# LM35.net
KiCad netlist of a schematic drawn in Altium Designer
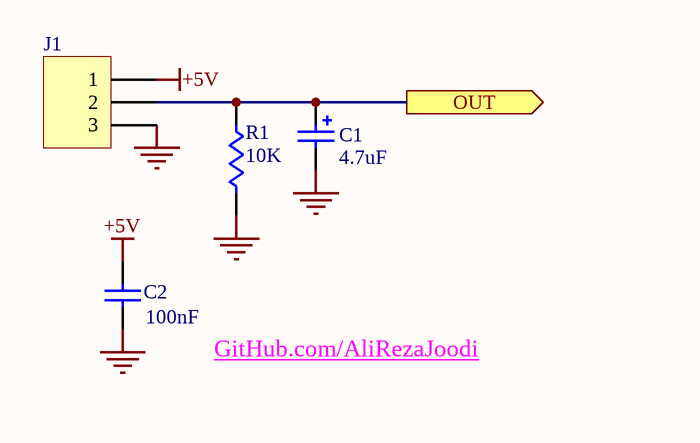
[diagram p0: LM35.SchDoc]

(export (version "E")
  (design (tool "Eeschema 10.0.6"))
  (components
    (comp (ref "C1")
      (value "4.7uF")
      (footprint "CAPPR2.5-6.3x5")
      (description "Polarized Capacitor (Radial)")
      (fields
        (field (name "MANUFACTURER") "Generic Components")
        (field (name "Comment") "Capacitor")
        (field (name "PUBLISHER") "Altium Limited")
      )
      (libsource (lib "Miscellaneous Devices") (part "Cap Pol1"))
    )
    (comp (ref "C2")
      (value "100nF")
      (footprint "CAPNTO2.54-3.05x1.78A")
      (description "Capacitor")
      (fields (field (name "PUBLISHER") "Altium Limited"))
      (libsource (lib "Miscellaneous Devices") (part "Cap"))
    )
    (comp (ref "J1")
      (value "Header")
      (footprint "Fonics_3PIN_1")
      (description "Header, 3-Pin")
      (fields (field (name "MANUFACTURER") "Generic Components") (field (name "PUBLISHER") "Altium Limited"))
      (libsource (lib "Miscellaneous Connectors") (part "Header 3"))
    )
    (comp (ref "R1")
      (value "10K")
      (footprint "AXIAL-0.4")
      (description "Resistor")
      (fields (field (name "MANUFACTURER") "Generic Components") (field (name "PUBLISHER") "Altium Limited"))
      (libsource (lib "Miscellaneous Devices") (part "Res1"))
    )
  )
  (nets
    (net (code "1") (name "+5V") (class "Default")
      (node (ref "C2") (pin "1") (pinfunction "1_1") (pintype "passive"))
      (node (ref "J1") (pin "1") (pinfunction "1_1") (pintype "passive"))
    )
    (net (code "2") (name "/OUT") (class "Default")
      (node (ref "C1") (pin "1") (pinfunction "1_1") (pintype "passive"))
      (node (ref "J1") (pin "2") (pinfunction "2_2") (pintype "passive"))
      (node (ref "R1") (pin "1") (pinfunction "1_1") (pintype "passive"))
    )
    (net (code "3") (name "GND") (class "Default")
      (node (ref "C1") (pin "2") (pinfunction "2_2") (pintype "passive"))
      (node (ref "C2") (pin "2") (pinfunction "2_2") (pintype "passive"))
      (node (ref "J1") (pin "3") (pinfunction "3_3") (pintype "passive"))
      (node (ref "R1") (pin "2") (pinfunction "2_2") (pintype "passive"))
    )
  )
)
